# bt_mod.net
KiCad netlist of a schematic drawn in EAGLE
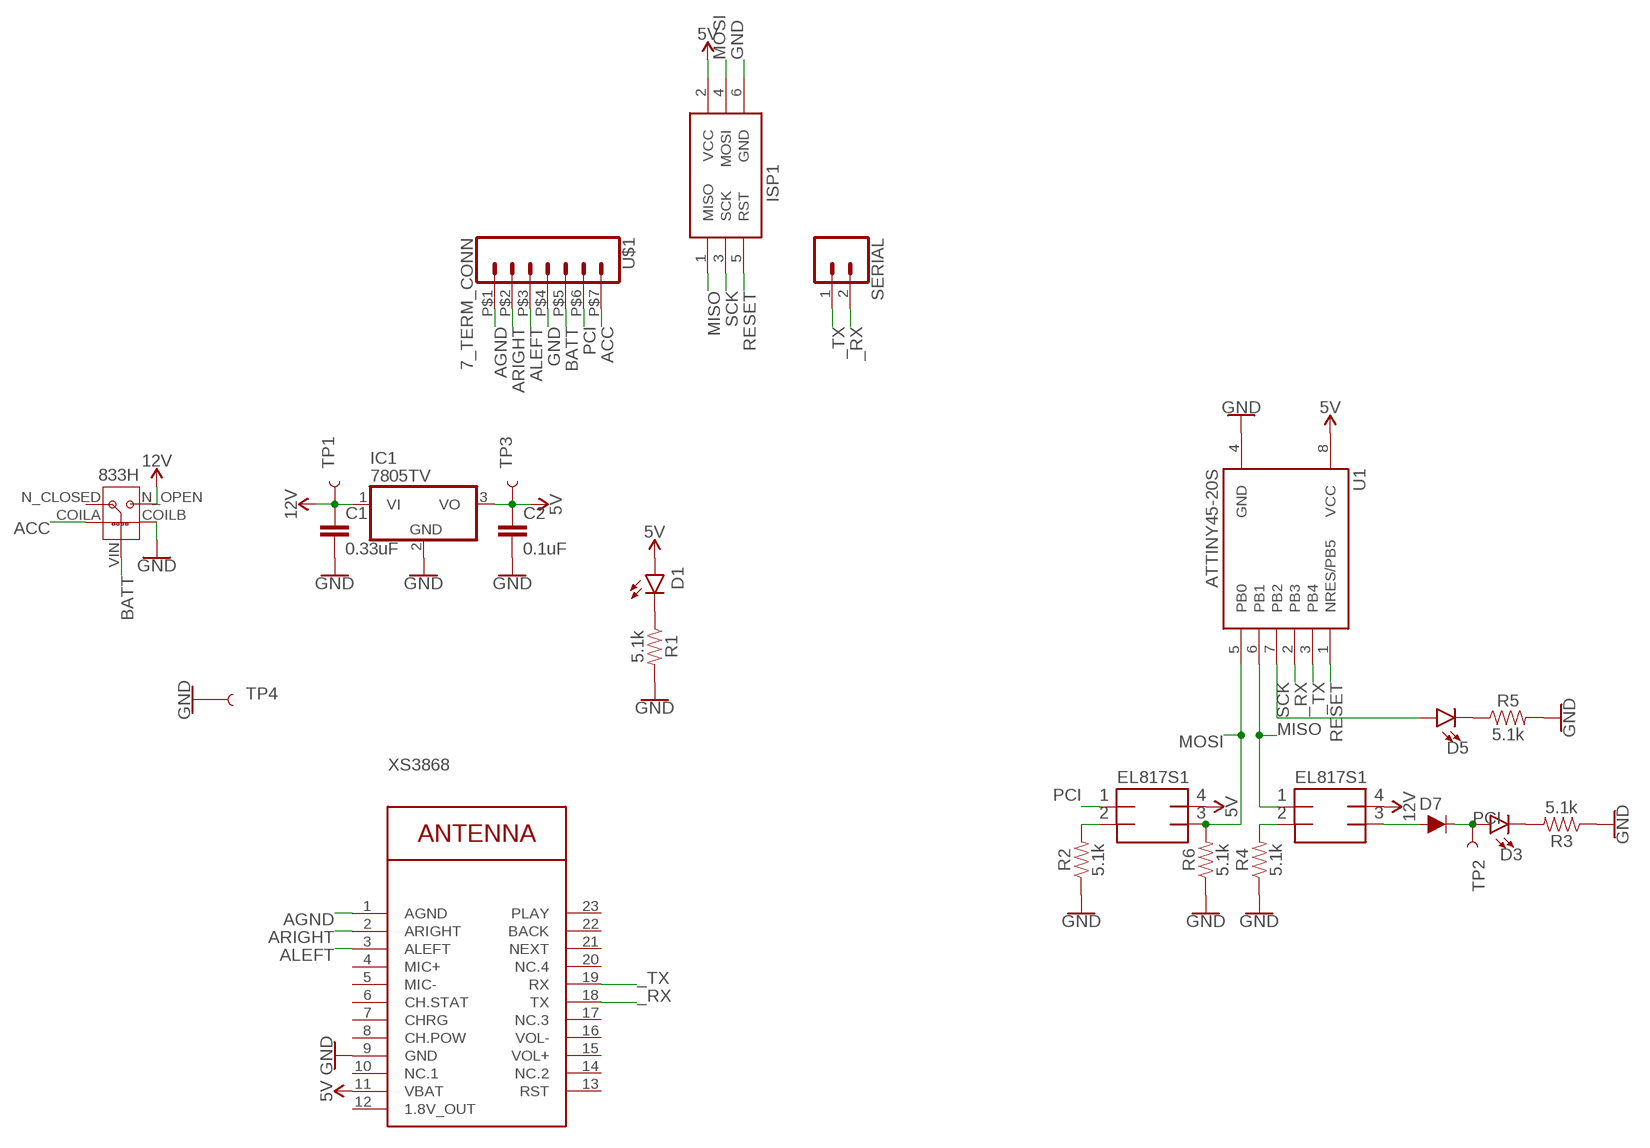
[diagram p0: schematic, sheet 1]

(export (version "E")
  (design (tool "Eeschema 10.0.6"))
  (components
    (comp (ref "1")
      (value "833H-1C-C-12VDC")
      (footprint "eagle-import:833H-1C-C-12VDC")
      (libsource (lib "eagle-import") (part "833H-1C-C-12VDC"))
    )
    (comp (ref "C1")
      (value "0.33uF")
      (footprint "eagle-import:0603")
      (libsource (lib "eagle-import") (part "0.1UF-0603-25V-(+80/-20%)"))
    )
    (comp (ref "C2")
      (value "0.1uF")
      (footprint "eagle-import:0603")
      (libsource (lib "eagle-import") (part "0.1UF-0603-25V-(+80/-20%)"))
    )
    (comp (ref "D1")
      (value "LED0603")
      (footprint "eagle-import:LED-0603")
      (libsource (lib "eagle-import") (part "LED0603"))
    )
    (comp (ref "D3")
      (value "LED0603")
      (footprint "eagle-import:LED-0603")
      (libsource (lib "eagle-import") (part "LED0603"))
    )
    (comp (ref "D5")
      (value "LED0603")
      (footprint "eagle-import:LED-0603")
      (libsource (lib "eagle-import") (part "LED0603"))
    )
    (comp (ref "D7")
      (value "250mA/100V")
      (footprint "eagle-import:SOD-323")
      (libsource (lib "eagle-import") (part "DIODE-BAS16J"))
    )
    (comp (ref "IC1")
      (value "7805TV")
      (footprint "eagle-import:TO220V")
      (libsource (lib "eagle-import") (part "78TV05"))
    )
    (comp (ref "INPUT")
      (value "EL3H7-G")
      (footprint "eagle-import:SMD-4")
      (libsource (lib "eagle-import") (part "EL3H7-G"))
    )
    (comp (ref "ISP1")
      (value "AVRISP-6")
      (footprint "eagle-import:AVRISP")
      (libsource (lib "eagle-import") (part "AVRISP-6"))
    )
    (comp (ref "OUTPUT")
      (value "EL3H7-G")
      (footprint "eagle-import:SMD-4")
      (libsource (lib "eagle-import") (part "EL3H7-G"))
    )
    (comp (ref "R1")
      (value "5.1k")
      (footprint "eagle-import:0603")
      (libsource (lib "eagle-import") (part "5.1KOHM5.1KOHM-0603-1/10W-1%"))
    )
    (comp (ref "R2")
      (value "5.1k")
      (footprint "eagle-import:0603")
      (libsource (lib "eagle-import") (part "5.1KOHM5.1KOHM-0603-1/10W-1%"))
    )
    (comp (ref "R3")
      (value "5.1k")
      (footprint "eagle-import:0603")
      (libsource (lib "eagle-import") (part "5.1KOHM5.1KOHM-0603-1/10W-1%"))
    )
    (comp (ref "R4")
      (value "5.1k")
      (footprint "eagle-import:0603")
      (libsource (lib "eagle-import") (part "5.1KOHM5.1KOHM-0603-1/10W-1%"))
    )
    (comp (ref "R5")
      (value "5.1k")
      (footprint "eagle-import:0603")
      (libsource (lib "eagle-import") (part "5.1KOHM5.1KOHM-0603-1/10W-1%"))
    )
    (comp (ref "R6")
      (value "5.1k")
      (footprint "eagle-import:0603")
      (libsource (lib "eagle-import") (part "5.1KOHM5.1KOHM-0603-1/10W-1%"))
    )
    (comp (ref "SERIAL")
      (value "CONN_02")
      (footprint "eagle-import:1X02")
      (libsource (lib "eagle-import") (part "CONN_02"))
    )
    (comp (ref "TP1")
      (value "TEST-POINT3X5")
      (footprint "eagle-import:PAD.03X.05")
      (libsource (lib "eagle-import") (part "TEST-POINT3X5"))
    )
    (comp (ref "TP2")
      (value "TEST-POINT3X5")
      (footprint "eagle-import:PAD.03X.05")
      (libsource (lib "eagle-import") (part "TEST-POINT3X5"))
    )
    (comp (ref "TP3")
      (value "TEST-POINT3X5")
      (footprint "eagle-import:PAD.03X.05")
      (libsource (lib "eagle-import") (part "TEST-POINT3X5"))
    )
    (comp (ref "TP4")
      (value "TEST-POINT3X5")
      (footprint "eagle-import:PAD.03X.05")
      (libsource (lib "eagle-import") (part "TEST-POINT3X5"))
    )
    (comp (ref "U$1")
      (value "7_TERM_CONN")
      (footprint "eagle-import:7_TERMINALS")
      (libsource (lib "eagle-import") (part "7_TERM_CONN"))
    )
    (comp (ref "U1")
      (value "ATTINY45-20S")
      (footprint "eagle-import:SOIC8_EIAJ_208MIL")
      (libsource (lib "eagle-import") (part "ATTINY45S-20"))
    )
    (comp (ref "XS3868")
      (value "WIRELESS-BLUETOOTH-XS3868")
      (footprint "eagle-import:WIRELESS-BLUETOOTH-XS3868")
      (libsource (lib "eagle-import") (part "WIRELESS-BLUETOOTH-XS3868"))
    )
  )
  (nets
    (net (code "1") (name "/1.8V_OUT") (class "Default")
      (node (ref "XS3868") (pin "12") (pinfunction "1.8V_OUT_12") (pintype "power_in"))
    )
    (net (code "2") (name "/ACC") (class "Default")
      (node (ref "1") (pin "COILA") (pinfunction "COILA_COILA") (pintype "bidirectional"))
      (node (ref "U$1") (pin "P$7") (pinfunction "7_P$7") (pintype "passive"))
    )
    (net (code "3") (name "/AGND") (class "Default")
      (node (ref "U$1") (pin "P$1") (pinfunction "1_P$1") (pintype "passive"))
      (node (ref "XS3868") (pin "1") (pinfunction "AGND_1") (pintype "power_in"))
    )
    (net (code "4") (name "/ALEFT") (class "Default")
      (node (ref "U$1") (pin "P$3") (pinfunction "3_P$3") (pintype "passive"))
      (node (ref "XS3868") (pin "3") (pinfunction "ALEFT_3") (pintype "output"))
    )
    (net (code "5") (name "/ARIGHT") (class "Default")
      (node (ref "U$1") (pin "P$2") (pinfunction "2_P$2") (pintype "passive"))
      (node (ref "XS3868") (pin "2") (pinfunction "ARIGHT_2") (pintype "output"))
    )
    (net (code "6") (name "/BATT") (class "Default")
      (node (ref "1") (pin "VIN") (pinfunction "VIN_VIN") (pintype "bidirectional"))
      (node (ref "U$1") (pin "P$5") (pinfunction "5_P$5") (pintype "passive"))
    )
    (net (code "7") (name "/MISO") (class "Default")
      (node (ref "ISP1") (pin "1") (pinfunction "MISO_1") (pintype "input"))
      (node (ref "OUTPUT") (pin "P$1") (pinfunction "P$1_P$1") (pintype "bidirectional"))
      (node (ref "U1") (pin "6") (pinfunction "PB1_6") (pintype "bidirectional"))
    )
    (net (code "8") (name "/MOSI") (class "Default")
      (node (ref "INPUT") (pin "P$3") (pinfunction "P$3_P$3") (pintype "bidirectional"))
      (node (ref "ISP1") (pin "4") (pinfunction "MOSI_4") (pintype "output"))
      (node (ref "R6") (pin "2") (pinfunction "2_2") (pintype "passive"))
      (node (ref "U1") (pin "5") (pinfunction "PB0_5") (pintype "bidirectional"))
    )
    (net (code "9") (name "/PCI") (class "Default")
      (node (ref "D3") (pin "A") (pinfunction "A_A") (pintype "passive"))
      (node (ref "D7") (pin "C") (pinfunction "C_C") (pintype "passive"))
      (node (ref "INPUT") (pin "P$1") (pinfunction "P$1_P$1") (pintype "bidirectional"))
      (node (ref "TP2") (pin "P$1") (pinfunction "1_P$1") (pintype "bidirectional"))
      (node (ref "U$1") (pin "P$6") (pinfunction "6_P$6") (pintype "passive"))
    )
    (net (code "10") (name "/RESET") (class "Default")
      (node (ref "ISP1") (pin "5") (pinfunction "RST_5") (pintype "output"))
      (node (ref "U1") (pin "1") (pinfunction "NRES/PB5_1") (pintype "bidirectional"))
    )
    (net (code "11") (name "/RST") (class "Default")
      (node (ref "XS3868") (pin "13") (pinfunction "RST_13") (pintype "power_in"))
    )
    (net (code "12") (name "/SCK") (class "Default")
      (node (ref "D5") (pin "A") (pinfunction "A_A") (pintype "passive"))
      (node (ref "ISP1") (pin "3") (pinfunction "SCK_3") (pintype "output"))
      (node (ref "U1") (pin "7") (pinfunction "PB2_7") (pintype "bidirectional"))
    )
    (net (code "13") (name "/_RX") (class "Default")
      (node (ref "SERIAL") (pin "2") (pinfunction "2_2") (pintype "passive"))
      (node (ref "U1") (pin "2") (pinfunction "PB3_2") (pintype "bidirectional"))
      (node (ref "XS3868") (pin "18") (pinfunction "TX_18") (pintype "bidirectional"))
    )
    (net (code "14") (name "/_TX") (class "Default")
      (node (ref "SERIAL") (pin "1") (pinfunction "1_1") (pintype "passive"))
      (node (ref "U1") (pin "3") (pinfunction "PB4_3") (pintype "bidirectional"))
      (node (ref "XS3868") (pin "19") (pinfunction "RX_19") (pintype "bidirectional"))
    )
    (net (code "15") (name "5V") (class "Default")
      (node (ref "C2") (pin "1") (pinfunction "1_1") (pintype "passive"))
      (node (ref "D1") (pin "A") (pinfunction "A_A") (pintype "passive"))
      (node (ref "IC1") (pin "3") (pinfunction "VO_3") (pintype "passive"))
      (node (ref "INPUT") (pin "P$4") (pinfunction "P$4_P$4") (pintype "bidirectional"))
      (node (ref "ISP1") (pin "2") (pinfunction "VCC_2") (pintype "power_in"))
      (node (ref "TP3") (pin "P$1") (pinfunction "1_P$1") (pintype "bidirectional"))
      (node (ref "U1") (pin "8") (pinfunction "VCC_8") (pintype "power_in"))
      (node (ref "XS3868") (pin "11") (pinfunction "VBAT_11") (pintype "power_in"))
    )
    (net (code "16") (name "12V") (class "Default")
      (node (ref "1") (pin "N_OPEN") (pinfunction "N_OPEN_N_OPEN") (pintype "bidirectional"))
      (node (ref "C1") (pin "1") (pinfunction "1_1") (pintype "passive"))
      (node (ref "IC1") (pin "1") (pinfunction "VI_1") (pintype "input"))
      (node (ref "OUTPUT") (pin "P$4") (pinfunction "P$4_P$4") (pintype "bidirectional"))
      (node (ref "TP1") (pin "P$1") (pinfunction "1_P$1") (pintype "bidirectional"))
    )
    (net (code "17") (name "GND") (class "Default")
      (node (ref "1") (pin "COILB") (pinfunction "COILB_COILB") (pintype "bidirectional"))
      (node (ref "C1") (pin "2") (pinfunction "2_2") (pintype "passive"))
      (node (ref "C2") (pin "2") (pinfunction "2_2") (pintype "passive"))
      (node (ref "IC1") (pin "2") (pinfunction "GND_2") (pintype "passive"))
      (node (ref "ISP1") (pin "6") (pinfunction "GND_6") (pintype "power_in"))
      (node (ref "R1") (pin "2") (pinfunction "2_2") (pintype "passive"))
      (node (ref "R2") (pin "1") (pinfunction "1_1") (pintype "passive"))
      (node (ref "R3") (pin "1") (pinfunction "1_1") (pintype "passive"))
      (node (ref "R4") (pin "1") (pinfunction "1_1") (pintype "passive"))
      (node (ref "R5") (pin "2") (pinfunction "2_2") (pintype "passive"))
      (node (ref "R6") (pin "1") (pinfunction "1_1") (pintype "passive"))
      (node (ref "TP4") (pin "P$1") (pinfunction "1_P$1") (pintype "bidirectional"))
      (node (ref "U$1") (pin "P$4") (pinfunction "4_P$4") (pintype "passive"))
      (node (ref "U1") (pin "4") (pinfunction "GND_4") (pintype "power_in"))
      (node (ref "XS3868") (pin "9") (pinfunction "GND_9") (pintype "power_in"))
    )
    (net (code "18") (name "Net-(D1-PadC)") (class "Default")
      (node (ref "D1") (pin "C") (pinfunction "C_C") (pintype "passive"))
      (node (ref "R1") (pin "1") (pinfunction "1_1") (pintype "passive"))
    )
    (net (code "19") (name "Net-(D3-PadC)") (class "Default")
      (node (ref "D3") (pin "C") (pinfunction "C_C") (pintype "passive"))
      (node (ref "R3") (pin "2") (pinfunction "2_2") (pintype "passive"))
    )
    (net (code "20") (name "Net-(D5-PadC)") (class "Default")
      (node (ref "D5") (pin "C") (pinfunction "C_C") (pintype "passive"))
      (node (ref "R5") (pin "1") (pinfunction "1_1") (pintype "passive"))
    )
    (net (code "21") (name "Net-(D7-PadA)") (class "Default")
      (node (ref "D7") (pin "A") (pinfunction "A_A") (pintype "passive"))
      (node (ref "OUTPUT") (pin "P$3") (pinfunction "P$3_P$3") (pintype "bidirectional"))
    )
    (net (code "22") (name "Net-(INPUT-PadP$2)") (class "Default")
      (node (ref "INPUT") (pin "P$2") (pinfunction "P$2_P$2") (pintype "bidirectional"))
      (node (ref "R2") (pin "2") (pinfunction "2_2") (pintype "passive"))
    )
    (net (code "23") (name "Net-(OUTPUT-PadP$2)") (class "Default")
      (node (ref "OUTPUT") (pin "P$2") (pinfunction "P$2_P$2") (pintype "bidirectional"))
      (node (ref "R4") (pin "2") (pinfunction "2_2") (pintype "passive"))
    )
    (net (code "24") (name "unconnected-(1-PadN_CLOSED)") (class "Default")
      (node (ref "1") (pin "N_CLOSED") (pinfunction "N_CLOSED_N_CLOSED") (pintype "bidirectional"))
    )
    (net (code "25") (name "unconnected-(XS3868-BACK-Pad22)") (class "Default")
      (node (ref "XS3868") (pin "22") (pinfunction "BACK_22") (pintype "bidirectional"))
    )
    (net (code "26") (name "unconnected-(XS3868-CH.POW-Pad8)") (class "Default")
      (node (ref "XS3868") (pin "8") (pinfunction "CH.POW_8") (pintype "bidirectional"))
    )
    (net (code "27") (name "unconnected-(XS3868-CH.STAT-Pad6)") (class "Default")
      (node (ref "XS3868") (pin "6") (pinfunction "CH.STAT_6") (pintype "bidirectional"))
    )
    (net (code "28") (name "unconnected-(XS3868-CHRG-Pad7)") (class "Default")
      (node (ref "XS3868") (pin "7") (pinfunction "CHRG_7") (pintype "bidirectional"))
    )
    (net (code "29") (name "unconnected-(XS3868-MIC+-Pad4)") (class "Default")
      (node (ref "XS3868") (pin "4") (pinfunction "MIC+_4") (pintype "bidirectional"))
    )
    (net (code "30") (name "unconnected-(XS3868-MIC--Pad5)") (class "Default")
      (node (ref "XS3868") (pin "5") (pinfunction "MIC-_5") (pintype "bidirectional"))
    )
    (net (code "31") (name "unconnected-(XS3868-NC.1-Pad10)") (class "Default")
      (node (ref "XS3868") (pin "10") (pinfunction "NC.1_10") (pintype "passive"))
    )
    (net (code "32") (name "unconnected-(XS3868-NC.2-Pad14)") (class "Default")
      (node (ref "XS3868") (pin "14") (pinfunction "NC.2_14") (pintype "passive"))
    )
    (net (code "33") (name "unconnected-(XS3868-NC.3-Pad17)") (class "Default")
      (node (ref "XS3868") (pin "17") (pinfunction "NC.3_17") (pintype "passive"))
    )
    (net (code "34") (name "unconnected-(XS3868-NC.4-Pad20)") (class "Default")
      (node (ref "XS3868") (pin "20") (pinfunction "NC.4_20") (pintype "passive"))
    )
    (net (code "35") (name "unconnected-(XS3868-NEXT-Pad21)") (class "Default")
      (node (ref "XS3868") (pin "21") (pinfunction "NEXT_21") (pintype "bidirectional"))
    )
    (net (code "36") (name "unconnected-(XS3868-PLAY-Pad23)") (class "Default")
      (node (ref "XS3868") (pin "23") (pinfunction "PLAY_23") (pintype "bidirectional"))
    )
    (net (code "37") (name "unconnected-(XS3868-VOL+-Pad15)") (class "Default")
      (node (ref "XS3868") (pin "15") (pinfunction "VOL+_15") (pintype "bidirectional"))
    )
    (net (code "38") (name "unconnected-(XS3868-VOL--Pad16)") (class "Default")
      (node (ref "XS3868") (pin "16") (pinfunction "VOL-_16") (pintype "bidirectional"))
    )
  )
)
